# stereo_mix_front.net
KiCad netlist of a schematic drawn in EAGLE
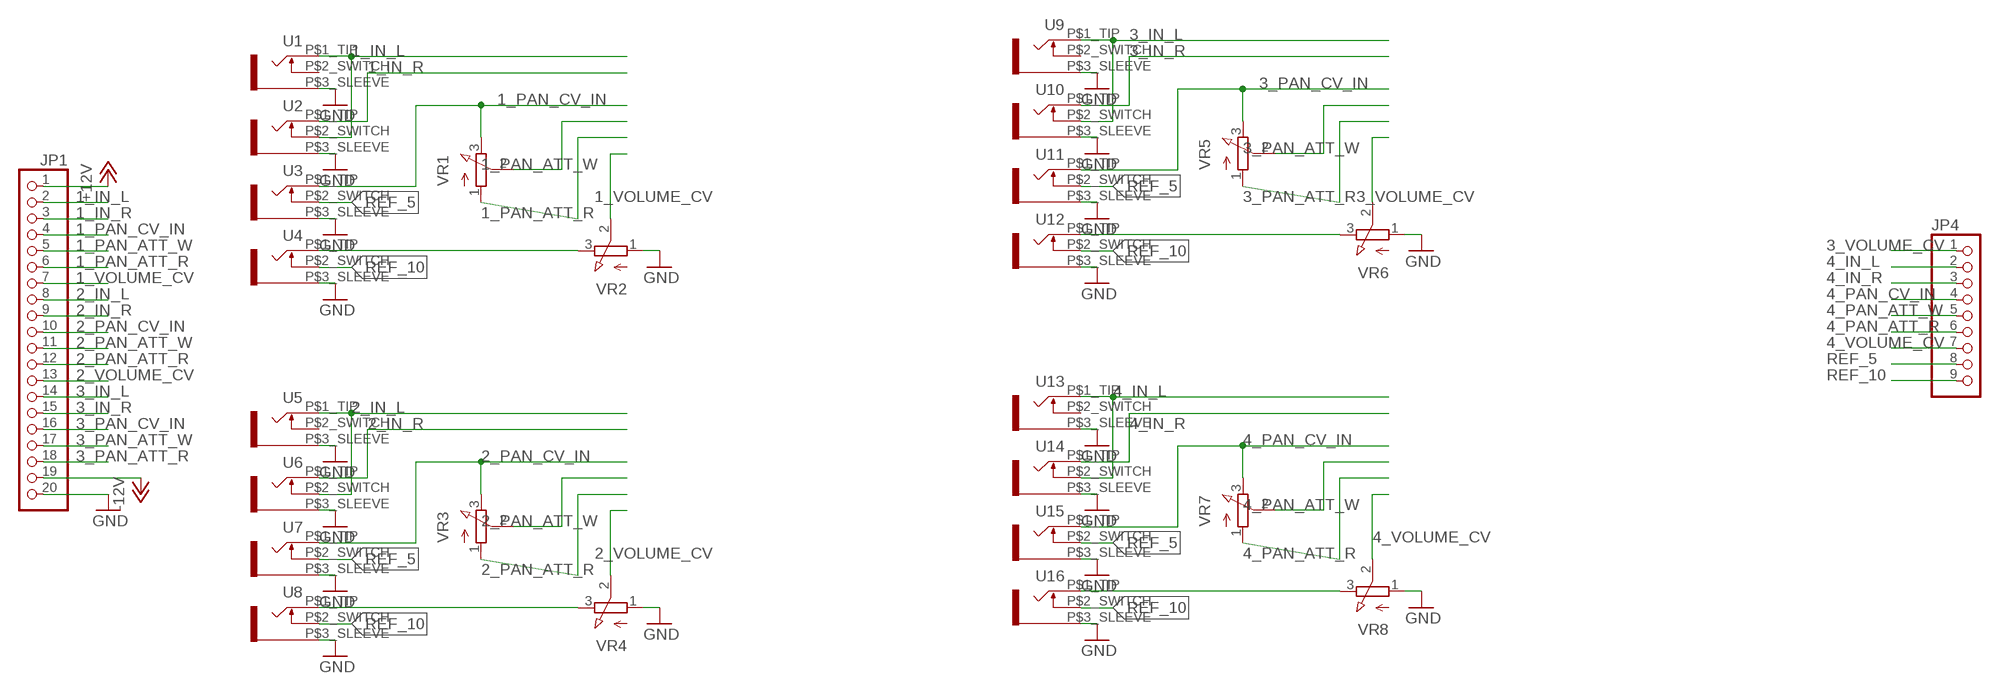
[diagram p0: schematic, sheet 1]
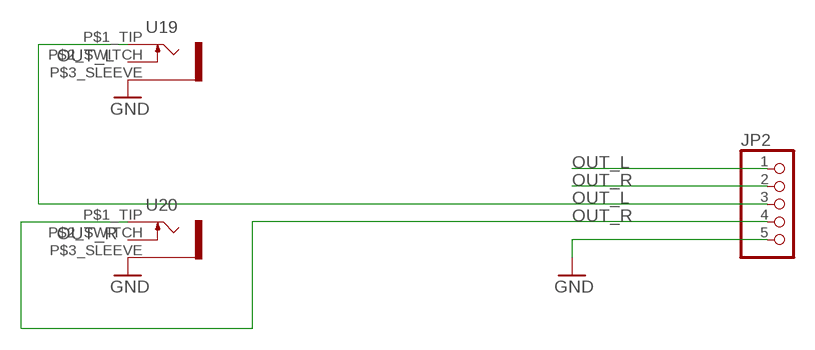
[diagram p1: schematic, sheet 2]

(export (version "E")
  (design (tool "Eeschema 10.0.6"))
  (components
    (comp (ref "JP1")
      (value "PINHD-1X20")
      (footprint "eagle-import:1X20")
      (libsource (lib "eagle-import") (part "PINHD-1X20"))
    )
    (comp (ref "JP4")
      (value "PINHD-1X9")
      (footprint "eagle-import:1X09")
      (libsource (lib "eagle-import") (part "PINHD-1X9"))
    )
    (comp (ref "U1")
      (value "WQP-PJ301M-12_JACK")
      (footprint "eagle-import:WQP-PJ301M-12_JACK")
      (libsource (lib "eagle-import") (part "WQP-PJ301M-12_JACK"))
    )
    (comp (ref "U2")
      (value "WQP-PJ301M-12_JACK")
      (footprint "eagle-import:WQP-PJ301M-12_JACK")
      (libsource (lib "eagle-import") (part "WQP-PJ301M-12_JACK"))
    )
    (comp (ref "U3")
      (value "WQP-PJ301M-12_JACK")
      (footprint "eagle-import:WQP-PJ301M-12_JACK")
      (libsource (lib "eagle-import") (part "WQP-PJ301M-12_JACK"))
    )
    (comp (ref "U4")
      (value "WQP-PJ301M-12_JACK")
      (footprint "eagle-import:WQP-PJ301M-12_JACK")
      (libsource (lib "eagle-import") (part "WQP-PJ301M-12_JACK"))
    )
    (comp (ref "U5")
      (value "WQP-PJ301M-12_JACK")
      (footprint "eagle-import:WQP-PJ301M-12_JACK")
      (libsource (lib "eagle-import") (part "WQP-PJ301M-12_JACK"))
    )
    (comp (ref "U6")
      (value "WQP-PJ301M-12_JACK")
      (footprint "eagle-import:WQP-PJ301M-12_JACK")
      (libsource (lib "eagle-import") (part "WQP-PJ301M-12_JACK"))
    )
    (comp (ref "U7")
      (value "WQP-PJ301M-12_JACK")
      (footprint "eagle-import:WQP-PJ301M-12_JACK")
      (libsource (lib "eagle-import") (part "WQP-PJ301M-12_JACK"))
    )
    (comp (ref "U8")
      (value "WQP-PJ301M-12_JACK")
      (footprint "eagle-import:WQP-PJ301M-12_JACK")
      (libsource (lib "eagle-import") (part "WQP-PJ301M-12_JACK"))
    )
    (comp (ref "U9")
      (value "WQP-PJ301M-12_JACK")
      (footprint "eagle-import:WQP-PJ301M-12_JACK")
      (libsource (lib "eagle-import") (part "WQP-PJ301M-12_JACK"))
    )
    (comp (ref "U10")
      (value "WQP-PJ301M-12_JACK")
      (footprint "eagle-import:WQP-PJ301M-12_JACK")
      (libsource (lib "eagle-import") (part "WQP-PJ301M-12_JACK"))
    )
    (comp (ref "U11")
      (value "WQP-PJ301M-12_JACK")
      (footprint "eagle-import:WQP-PJ301M-12_JACK")
      (libsource (lib "eagle-import") (part "WQP-PJ301M-12_JACK"))
    )
    (comp (ref "U12")
      (value "WQP-PJ301M-12_JACK")
      (footprint "eagle-import:WQP-PJ301M-12_JACK")
      (libsource (lib "eagle-import") (part "WQP-PJ301M-12_JACK"))
    )
    (comp (ref "U13")
      (value "WQP-PJ301M-12_JACK")
      (footprint "eagle-import:WQP-PJ301M-12_JACK")
      (libsource (lib "eagle-import") (part "WQP-PJ301M-12_JACK"))
    )
    (comp (ref "U14")
      (value "WQP-PJ301M-12_JACK")
      (footprint "eagle-import:WQP-PJ301M-12_JACK")
      (libsource (lib "eagle-import") (part "WQP-PJ301M-12_JACK"))
    )
    (comp (ref "U15")
      (value "WQP-PJ301M-12_JACK")
      (footprint "eagle-import:WQP-PJ301M-12_JACK")
      (libsource (lib "eagle-import") (part "WQP-PJ301M-12_JACK"))
    )
    (comp (ref "U16")
      (value "WQP-PJ301M-12_JACK")
      (footprint "eagle-import:WQP-PJ301M-12_JACK")
      (libsource (lib "eagle-import") (part "WQP-PJ301M-12_JACK"))
    )
    (comp (ref "VR1")
      (value "9MM_SNAP-IN_POT_")
      (footprint "eagle-import:9MM_SNAP-IN_POT")
      (fields (field (name "SPICEPREFIX") "J"))
      (libsource (lib "eagle-import") (part "9MM_SNAP-IN_POT_"))
    )
    (comp (ref "VR2")
      (value "9MM_SNAP-IN_POT_")
      (footprint "eagle-import:9MM_SNAP-IN_POT")
      (fields (field (name "SPICEPREFIX") "J"))
      (libsource (lib "eagle-import") (part "9MM_SNAP-IN_POT_"))
    )
    (comp (ref "VR3")
      (value "9MM_SNAP-IN_POT_")
      (footprint "eagle-import:9MM_SNAP-IN_POT")
      (fields (field (name "SPICEPREFIX") "J"))
      (libsource (lib "eagle-import") (part "9MM_SNAP-IN_POT_"))
    )
    (comp (ref "VR4")
      (value "9MM_SNAP-IN_POT_")
      (footprint "eagle-import:9MM_SNAP-IN_POT")
      (fields (field (name "SPICEPREFIX") "J"))
      (libsource (lib "eagle-import") (part "9MM_SNAP-IN_POT_"))
    )
    (comp (ref "VR5")
      (value "9MM_SNAP-IN_POT_")
      (footprint "eagle-import:9MM_SNAP-IN_POT")
      (fields (field (name "SPICEPREFIX") "J"))
      (libsource (lib "eagle-import") (part "9MM_SNAP-IN_POT_"))
    )
    (comp (ref "VR6")
      (value "9MM_SNAP-IN_POT_")
      (footprint "eagle-import:9MM_SNAP-IN_POT")
      (fields (field (name "SPICEPREFIX") "J"))
      (libsource (lib "eagle-import") (part "9MM_SNAP-IN_POT_"))
    )
    (comp (ref "VR7")
      (value "9MM_SNAP-IN_POT_")
      (footprint "eagle-import:9MM_SNAP-IN_POT")
      (fields (field (name "SPICEPREFIX") "J"))
      (libsource (lib "eagle-import") (part "9MM_SNAP-IN_POT_"))
    )
    (comp (ref "VR8")
      (value "9MM_SNAP-IN_POT_")
      (footprint "eagle-import:9MM_SNAP-IN_POT")
      (fields (field (name "SPICEPREFIX") "J"))
      (libsource (lib "eagle-import") (part "9MM_SNAP-IN_POT_"))
    )
    (comp (ref "JP2")
      (value "PINHD-1X5")
      (footprint "eagle-import:1X05")
      (libsource (lib "eagle-import") (part "PINHD-1X5"))
    )
    (comp (ref "U19")
      (value "WQP-PJ301M-12_JACK")
      (footprint "eagle-import:WQP-PJ301M-12_JACK")
      (libsource (lib "eagle-import") (part "WQP-PJ301M-12_JACK"))
    )
    (comp (ref "U20")
      (value "WQP-PJ301M-12_JACK")
      (footprint "eagle-import:WQP-PJ301M-12_JACK")
      (libsource (lib "eagle-import") (part "WQP-PJ301M-12_JACK"))
    )
  )
  (nets
    (net (code "1") (name "+12V") (class "Default")
      (node (ref "JP1") (pin "1") (pinfunction "1_1") (pintype "passive"))
    )
    (net (code "2") (name "-12V") (class "Default")
      (node (ref "JP1") (pin "19") (pinfunction "19_19") (pintype "passive"))
    )
    (net (code "3") (name "1_IN_L") (class "Default")
      (node (ref "JP1") (pin "2") (pinfunction "2_2") (pintype "passive"))
      (node (ref "U1") (pin "P$1_TIP") (pinfunction "2_P$1_TIP") (pintype "passive"))
      (node (ref "U2") (pin "P$2_SWITCH") (pinfunction "3_P$2_SWITCH") (pintype "passive"))
    )
    (net (code "4") (name "1_IN_R") (class "Default")
      (node (ref "JP1") (pin "3") (pinfunction "3_3") (pintype "passive"))
      (node (ref "U2") (pin "P$1_TIP") (pinfunction "2_P$1_TIP") (pintype "passive"))
    )
    (net (code "5") (name "1_PAN_ATT_R") (class "Default")
      (node (ref "JP1") (pin "6") (pinfunction "6_6") (pintype "passive"))
      (node (ref "VR1") (pin "1") (pinfunction "A_1") (pintype "passive"))
    )
    (net (code "6") (name "1_PAN_ATT_W") (class "Default")
      (node (ref "JP1") (pin "5") (pinfunction "5_5") (pintype "passive"))
      (node (ref "VR1") (pin "2") (pinfunction "S_2") (pintype "passive"))
    )
    (net (code "7") (name "1_PAN_CV_IN") (class "Default")
      (node (ref "JP1") (pin "4") (pinfunction "4_4") (pintype "passive"))
      (node (ref "U3") (pin "P$1_TIP") (pinfunction "2_P$1_TIP") (pintype "passive"))
      (node (ref "VR1") (pin "3") (pinfunction "E_3") (pintype "passive"))
    )
    (net (code "8") (name "1_VOLUME_CV") (class "Default")
      (node (ref "JP1") (pin "7") (pinfunction "7_7") (pintype "passive"))
      (node (ref "VR2") (pin "2") (pinfunction "S_2") (pintype "passive"))
    )
    (net (code "9") (name "2_IN_L") (class "Default")
      (node (ref "JP1") (pin "8") (pinfunction "8_8") (pintype "passive"))
      (node (ref "U5") (pin "P$1_TIP") (pinfunction "2_P$1_TIP") (pintype "passive"))
      (node (ref "U6") (pin "P$2_SWITCH") (pinfunction "3_P$2_SWITCH") (pintype "passive"))
    )
    (net (code "10") (name "2_IN_R") (class "Default")
      (node (ref "JP1") (pin "9") (pinfunction "9_9") (pintype "passive"))
      (node (ref "U6") (pin "P$1_TIP") (pinfunction "2_P$1_TIP") (pintype "passive"))
    )
    (net (code "11") (name "2_PAN_ATT_R") (class "Default")
      (node (ref "JP1") (pin "12") (pinfunction "12_12") (pintype "passive"))
      (node (ref "VR3") (pin "1") (pinfunction "A_1") (pintype "passive"))
    )
    (net (code "12") (name "2_PAN_ATT_W") (class "Default")
      (node (ref "JP1") (pin "11") (pinfunction "11_11") (pintype "passive"))
      (node (ref "VR3") (pin "2") (pinfunction "S_2") (pintype "passive"))
    )
    (net (code "13") (name "2_PAN_CV_IN") (class "Default")
      (node (ref "JP1") (pin "10") (pinfunction "10_10") (pintype "passive"))
      (node (ref "U7") (pin "P$1_TIP") (pinfunction "2_P$1_TIP") (pintype "passive"))
      (node (ref "VR3") (pin "3") (pinfunction "E_3") (pintype "passive"))
    )
    (net (code "14") (name "2_VOLUME_CV") (class "Default")
      (node (ref "JP1") (pin "13") (pinfunction "13_13") (pintype "passive"))
      (node (ref "VR4") (pin "2") (pinfunction "S_2") (pintype "passive"))
    )
    (net (code "15") (name "3_IN_L") (class "Default")
      (node (ref "JP1") (pin "14") (pinfunction "14_14") (pintype "passive"))
      (node (ref "U10") (pin "P$2_SWITCH") (pinfunction "3_P$2_SWITCH") (pintype "passive"))
      (node (ref "U9") (pin "P$1_TIP") (pinfunction "2_P$1_TIP") (pintype "passive"))
    )
    (net (code "16") (name "3_IN_R") (class "Default")
      (node (ref "JP1") (pin "15") (pinfunction "15_15") (pintype "passive"))
      (node (ref "U10") (pin "P$1_TIP") (pinfunction "2_P$1_TIP") (pintype "passive"))
    )
    (net (code "17") (name "3_PAN_ATT_R") (class "Default")
      (node (ref "JP1") (pin "18") (pinfunction "18_18") (pintype "passive"))
      (node (ref "VR5") (pin "1") (pinfunction "A_1") (pintype "passive"))
    )
    (net (code "18") (name "3_PAN_ATT_W") (class "Default")
      (node (ref "JP1") (pin "17") (pinfunction "17_17") (pintype "passive"))
      (node (ref "VR5") (pin "2") (pinfunction "S_2") (pintype "passive"))
    )
    (net (code "19") (name "3_PAN_CV_IN") (class "Default")
      (node (ref "JP1") (pin "16") (pinfunction "16_16") (pintype "passive"))
      (node (ref "U11") (pin "P$1_TIP") (pinfunction "2_P$1_TIP") (pintype "passive"))
      (node (ref "VR5") (pin "3") (pinfunction "E_3") (pintype "passive"))
    )
    (net (code "20") (name "3_VOLUME_CV") (class "Default")
      (node (ref "JP4") (pin "1") (pinfunction "1_1") (pintype "passive"))
      (node (ref "VR6") (pin "2") (pinfunction "S_2") (pintype "passive"))
    )
    (net (code "21") (name "4_IN_L") (class "Default")
      (node (ref "JP4") (pin "2") (pinfunction "2_2") (pintype "passive"))
      (node (ref "U13") (pin "P$1_TIP") (pinfunction "2_P$1_TIP") (pintype "passive"))
      (node (ref "U14") (pin "P$2_SWITCH") (pinfunction "3_P$2_SWITCH") (pintype "passive"))
    )
    (net (code "22") (name "4_IN_R") (class "Default")
      (node (ref "JP4") (pin "3") (pinfunction "3_3") (pintype "passive"))
      (node (ref "U14") (pin "P$1_TIP") (pinfunction "2_P$1_TIP") (pintype "passive"))
    )
    (net (code "23") (name "4_PAN_ATT_R") (class "Default")
      (node (ref "JP4") (pin "6") (pinfunction "6_6") (pintype "passive"))
      (node (ref "VR7") (pin "1") (pinfunction "A_1") (pintype "passive"))
    )
    (net (code "24") (name "4_PAN_ATT_W") (class "Default")
      (node (ref "JP4") (pin "5") (pinfunction "5_5") (pintype "passive"))
      (node (ref "VR7") (pin "2") (pinfunction "S_2") (pintype "passive"))
    )
    (net (code "25") (name "4_PAN_CV_IN") (class "Default")
      (node (ref "JP4") (pin "4") (pinfunction "4_4") (pintype "passive"))
      (node (ref "U15") (pin "P$1_TIP") (pinfunction "2_P$1_TIP") (pintype "passive"))
      (node (ref "VR7") (pin "3") (pinfunction "E_3") (pintype "passive"))
    )
    (net (code "26") (name "4_VOLUME_CV") (class "Default")
      (node (ref "JP4") (pin "7") (pinfunction "7_7") (pintype "passive"))
      (node (ref "VR8") (pin "2") (pinfunction "S_2") (pintype "passive"))
    )
    (net (code "27") (name "GND") (class "Default")
      (node (ref "JP1") (pin "20") (pinfunction "20_20") (pintype "passive"))
      (node (ref "JP2") (pin "5") (pinfunction "5_5") (pintype "passive"))
      (node (ref "U1") (pin "P$3_SLEEVE") (pinfunction "1_P$3_SLEEVE") (pintype "passive"))
      (node (ref "U10") (pin "P$3_SLEEVE") (pinfunction "1_P$3_SLEEVE") (pintype "passive"))
      (node (ref "U11") (pin "P$3_SLEEVE") (pinfunction "1_P$3_SLEEVE") (pintype "passive"))
      (node (ref "U12") (pin "P$3_SLEEVE") (pinfunction "1_P$3_SLEEVE") (pintype "passive"))
      (node (ref "U13") (pin "P$3_SLEEVE") (pinfunction "1_P$3_SLEEVE") (pintype "passive"))
      (node (ref "U14") (pin "P$3_SLEEVE") (pinfunction "1_P$3_SLEEVE") (pintype "passive"))
      (node (ref "U15") (pin "P$3_SLEEVE") (pinfunction "1_P$3_SLEEVE") (pintype "passive"))
      (node (ref "U16") (pin "P$3_SLEEVE") (pinfunction "1_P$3_SLEEVE") (pintype "passive"))
      (node (ref "U19") (pin "P$3_SLEEVE") (pinfunction "1_P$3_SLEEVE") (pintype "passive"))
      (node (ref "U2") (pin "P$3_SLEEVE") (pinfunction "1_P$3_SLEEVE") (pintype "passive"))
      (node (ref "U20") (pin "P$3_SLEEVE") (pinfunction "1_P$3_SLEEVE") (pintype "passive"))
      (node (ref "U3") (pin "P$3_SLEEVE") (pinfunction "1_P$3_SLEEVE") (pintype "passive"))
      (node (ref "U4") (pin "P$3_SLEEVE") (pinfunction "1_P$3_SLEEVE") (pintype "passive"))
      (node (ref "U5") (pin "P$3_SLEEVE") (pinfunction "1_P$3_SLEEVE") (pintype "passive"))
      (node (ref "U6") (pin "P$3_SLEEVE") (pinfunction "1_P$3_SLEEVE") (pintype "passive"))
      (node (ref "U7") (pin "P$3_SLEEVE") (pinfunction "1_P$3_SLEEVE") (pintype "passive"))
      (node (ref "U8") (pin "P$3_SLEEVE") (pinfunction "1_P$3_SLEEVE") (pintype "passive"))
      (node (ref "U9") (pin "P$3_SLEEVE") (pinfunction "1_P$3_SLEEVE") (pintype "passive"))
      (node (ref "VR2") (pin "1") (pinfunction "A_1") (pintype "passive"))
      (node (ref "VR4") (pin "1") (pinfunction "A_1") (pintype "passive"))
      (node (ref "VR6") (pin "1") (pinfunction "A_1") (pintype "passive"))
      (node (ref "VR8") (pin "1") (pinfunction "A_1") (pintype "passive"))
    )
    (net (code "28") (name "Net-(U4-2)") (class "Default")
      (node (ref "U4") (pin "P$1_TIP") (pinfunction "2_P$1_TIP") (pintype "passive"))
      (node (ref "VR2") (pin "3") (pinfunction "E_3") (pintype "passive"))
    )
    (net (code "29") (name "Net-(U8-2)") (class "Default")
      (node (ref "U8") (pin "P$1_TIP") (pinfunction "2_P$1_TIP") (pintype "passive"))
      (node (ref "VR4") (pin "3") (pinfunction "E_3") (pintype "passive"))
    )
    (net (code "30") (name "Net-(U12-2)") (class "Default")
      (node (ref "U12") (pin "P$1_TIP") (pinfunction "2_P$1_TIP") (pintype "passive"))
      (node (ref "VR6") (pin "3") (pinfunction "E_3") (pintype "passive"))
    )
    (net (code "31") (name "Net-(U16-2)") (class "Default")
      (node (ref "U16") (pin "P$1_TIP") (pinfunction "2_P$1_TIP") (pintype "passive"))
      (node (ref "VR8") (pin "3") (pinfunction "E_3") (pintype "passive"))
    )
    (net (code "32") (name "OUT_L") (class "Default")
      (node (ref "JP2") (pin "1") (pinfunction "1_1") (pintype "passive"))
      (node (ref "JP2") (pin "3") (pinfunction "3_3") (pintype "passive"))
      (node (ref "U19") (pin "P$1_TIP") (pinfunction "2_P$1_TIP") (pintype "passive"))
    )
    (net (code "33") (name "OUT_R") (class "Default")
      (node (ref "JP2") (pin "2") (pinfunction "2_2") (pintype "passive"))
      (node (ref "JP2") (pin "4") (pinfunction "4_4") (pintype "passive"))
      (node (ref "U20") (pin "P$1_TIP") (pinfunction "2_P$1_TIP") (pintype "passive"))
    )
    (net (code "34") (name "REF_5") (class "Default")
      (node (ref "JP4") (pin "8") (pinfunction "8_8") (pintype "passive"))
      (node (ref "U11") (pin "P$2_SWITCH") (pinfunction "3_P$2_SWITCH") (pintype "passive"))
      (node (ref "U15") (pin "P$2_SWITCH") (pinfunction "3_P$2_SWITCH") (pintype "passive"))
      (node (ref "U3") (pin "P$2_SWITCH") (pinfunction "3_P$2_SWITCH") (pintype "passive"))
      (node (ref "U7") (pin "P$2_SWITCH") (pinfunction "3_P$2_SWITCH") (pintype "passive"))
    )
    (net (code "35") (name "REF_10") (class "Default")
      (node (ref "JP4") (pin "9") (pinfunction "9_9") (pintype "passive"))
      (node (ref "U12") (pin "P$2_SWITCH") (pinfunction "3_P$2_SWITCH") (pintype "passive"))
      (node (ref "U16") (pin "P$2_SWITCH") (pinfunction "3_P$2_SWITCH") (pintype "passive"))
      (node (ref "U4") (pin "P$2_SWITCH") (pinfunction "3_P$2_SWITCH") (pintype "passive"))
      (node (ref "U8") (pin "P$2_SWITCH") (pinfunction "3_P$2_SWITCH") (pintype "passive"))
    )
    (net (code "36") (name "unconnected-(U1-3-PadP$2_SWITCH)") (class "Default")
      (node (ref "U1") (pin "P$2_SWITCH") (pinfunction "3_P$2_SWITCH") (pintype "passive"))
    )
    (net (code "37") (name "unconnected-(U5-3-PadP$2_SWITCH)") (class "Default")
      (node (ref "U5") (pin "P$2_SWITCH") (pinfunction "3_P$2_SWITCH") (pintype "passive"))
    )
    (net (code "38") (name "unconnected-(U9-3-PadP$2_SWITCH)") (class "Default")
      (node (ref "U9") (pin "P$2_SWITCH") (pinfunction "3_P$2_SWITCH") (pintype "passive"))
    )
    (net (code "39") (name "unconnected-(U13-3-PadP$2_SWITCH)") (class "Default")
      (node (ref "U13") (pin "P$2_SWITCH") (pinfunction "3_P$2_SWITCH") (pintype "passive"))
    )
    (net (code "40") (name "unconnected-(U19-3-PadP$2_SWITCH)") (class "Default")
      (node (ref "U19") (pin "P$2_SWITCH") (pinfunction "3_P$2_SWITCH") (pintype "passive"))
    )
    (net (code "41") (name "unconnected-(U20-3-PadP$2_SWITCH)") (class "Default")
      (node (ref "U20") (pin "P$2_SWITCH") (pinfunction "3_P$2_SWITCH") (pintype "passive"))
    )
  )
)
